# RiskChemi_Sensors_V2_11.net
KiCad netlist of a schematic drawn in Altium Designer
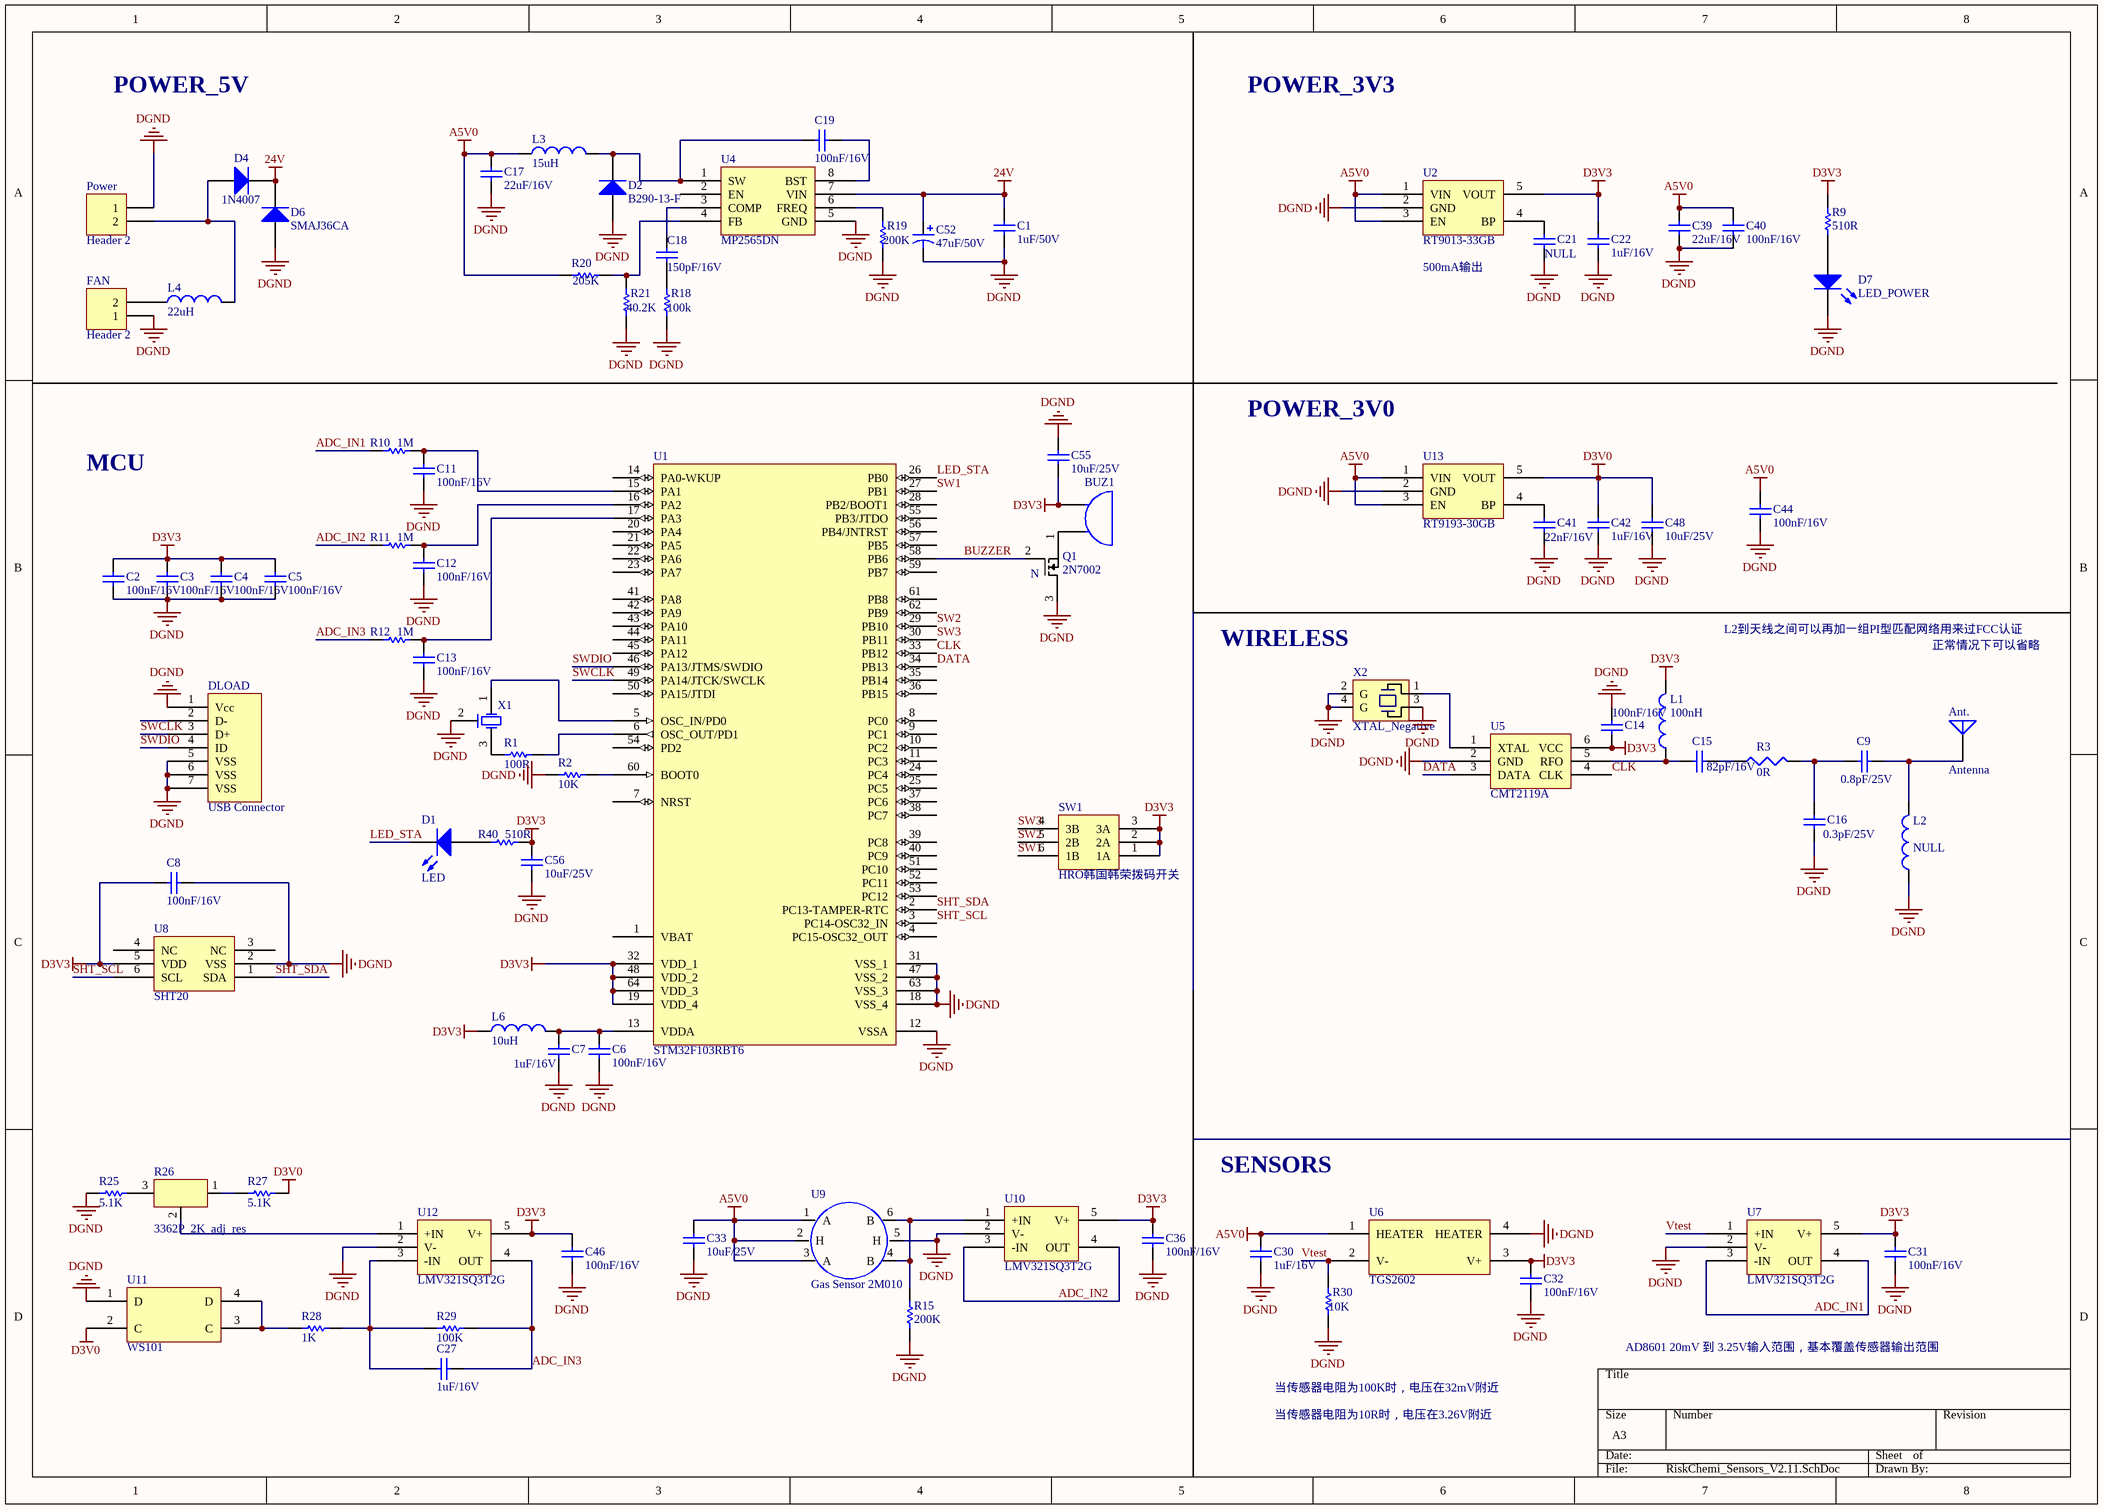
[diagram p0: RiskChemi_Sensors_V2.11.SchDoc]

(export (version "E")
  (design (tool "Eeschema 10.0.6"))
  (components
    (comp (ref "Ant.")
      (value "Antenna")
      (footprint "PIN1")
      (description "Generic Antenna")
      (fields (field (name "PUBLISHER") "Altium Limited"))
      (libsource (lib "Miscellaneous Devices") (part "Antenna"))
    )
    (comp (ref "BUZ1")
      (value "BUZZER 0905 through hole")
      (footprint "BUZ0905")
      (description "Buzzer")
      (libsource (lib "杂元件库") (part "BUZZER"))
    )
    (comp (ref "C1")
      (value "1uF/50V")
      (footprint "0805")
      (description "Capacitor")
      (fields (field (name "PUBLISHER") "Altium Limited"))
      (libsource (lib "Miscellaneous Devices") (part "Cap"))
    )
    (comp (ref "C2")
      (value "100nF/16V")
      (footprint "BinFeng:0603")
      (description "Capacitor")
      (fields (field (name "PUBLISHER") "Altium Limited"))
      (libsource (lib "Miscellaneous Devices") (part "Cap"))
    )
    (comp (ref "C3")
      (value "100nF/16V")
      (footprint "BinFeng:0603")
      (description "Capacitor")
      (fields (field (name "PUBLISHER") "Altium Limited"))
      (libsource (lib "Miscellaneous Devices") (part "Cap"))
    )
    (comp (ref "C4")
      (value "100nF/16V")
      (footprint "BinFeng:0603")
      (description "Capacitor")
      (fields (field (name "PUBLISHER") "Altium Limited"))
      (libsource (lib "Miscellaneous Devices") (part "Cap"))
    )
    (comp (ref "C5")
      (value "100nF/16V")
      (footprint "BinFeng:0603")
      (description "Capacitor")
      (fields (field (name "PUBLISHER") "Altium Limited"))
      (libsource (lib "Miscellaneous Devices") (part "Cap"))
    )
    (comp (ref "C6")
      (value "100nF/16V")
      (footprint "BinFeng:0603")
      (description "Capacitor")
      (fields (field (name "PUBLISHER") "Altium Limited"))
      (libsource (lib "Miscellaneous Devices") (part "Cap"))
    )
    (comp (ref "C7")
      (value "1uF/16V")
      (footprint "BinFeng:0603")
      (description "Capacitor")
      (fields (field (name "PUBLISHER") "Altium Limited"))
      (libsource (lib "Miscellaneous Devices") (part "Cap"))
    )
    (comp (ref "C8")
      (value "100nF/16V")
      (footprint "BinFeng:0603")
      (description "Capacitor")
      (fields (field (name "PUBLISHER") "Altium Limited"))
      (libsource (lib "Miscellaneous Devices") (part "Cap"))
    )
    (comp (ref "C9")
      (value "0.8pF/25V")
      (footprint "1608[0603]")
      (description "Capacitor (Semiconductor SIM Model)")
      (fields (field (name "PUBLISHER") "Altium Limited"))
      (libsource (lib "Miscellaneous Devices") (part "Cap Semi"))
    )
    (comp (ref "C11")
      (value "100nF/16V")
      (footprint "BinFeng:0603")
      (description "Capacitor")
      (fields (field (name "PUBLISHER") "Altium Limited"))
      (libsource (lib "Miscellaneous Devices") (part "Cap"))
    )
    (comp (ref "C12")
      (value "100nF/16V")
      (footprint "BinFeng:0603")
      (description "Capacitor")
      (fields (field (name "PUBLISHER") "Altium Limited"))
      (libsource (lib "Miscellaneous Devices") (part "Cap"))
    )
    (comp (ref "C13")
      (value "100nF/16V")
      (footprint "BinFeng:0603")
      (description "Capacitor")
      (fields (field (name "PUBLISHER") "Altium Limited"))
      (libsource (lib "Miscellaneous Devices") (part "Cap"))
    )
    (comp (ref "C14")
      (value "100nF/16V")
      (footprint "BinFeng:0402")
      (description "Capacitor")
      (fields (field (name "PUBLISHER") "Altium Limited"))
      (libsource (lib "Miscellaneous Devices") (part "Cap"))
    )
    (comp (ref "C15")
      (value "82pF/16V")
      (footprint "BinFeng:0402")
      (description "Capacitor")
      (fields (field (name "PUBLISHER") "Altium Limited"))
      (libsource (lib "Miscellaneous Devices") (part "Cap"))
    )
    (comp (ref "C16")
      (value "0.3pF/25V")
      (footprint "BinFeng:0402")
      (description "Capacitor")
      (fields (field (name "PUBLISHER") "Altium Limited"))
      (libsource (lib "Miscellaneous Devices") (part "Cap"))
    )
    (comp (ref "C17")
      (value "22uF/16V")
      (footprint "0805")
      (description "Capacitor,50V")
      (fields (field (name "PUBLISHER") "Altium Limited"))
      (libsource (lib "Miscellaneous Devices") (part "Cap"))
    )
    (comp (ref "C18")
      (value "150pF/16V")
      (footprint "BinFeng:0603")
      (description "Capacitor")
      (fields (field (name "PUBLISHER") "Altium Limited"))
      (libsource (lib "Miscellaneous Devices") (part "Cap"))
    )
    (comp (ref "C19")
      (value "100nF/16V")
      (footprint "BinFeng:0603")
      (description "Capacitor")
      (fields (field (name "PUBLISHER") "Altium Limited"))
      (libsource (lib "Miscellaneous Devices") (part "Cap"))
    )
    (comp (ref "C21")
      (value "NULL")
      (footprint "BinFeng:0402")
      (description "Capacitor")
      (fields (field (name "PUBLISHER") "Altium Limited"))
      (libsource (lib "Miscellaneous Devices") (part "Cap"))
    )
    (comp (ref "C22")
      (value "1uF/16V")
      (footprint "BinFeng:0402")
      (description "Capacitor")
      (fields (field (name "PUBLISHER") "Altium Limited"))
      (libsource (lib "Miscellaneous Devices") (part "Cap"))
    )
    (comp (ref "C27")
      (value "1uF/16V")
      (footprint "BinFeng:0603")
      (description "Capacitor")
      (fields (field (name "PUBLISHER") "Altium Limited"))
      (libsource (lib "Miscellaneous Devices") (part "Cap"))
    )
    (comp (ref "C30")
      (value "1uF/16V")
      (footprint "BinFeng:0603")
      (description "Capacitor")
      (fields (field (name "PUBLISHER") "Altium Limited"))
      (libsource (lib "Miscellaneous Devices") (part "Cap"))
    )
    (comp (ref "C31")
      (value "100nF/16V")
      (footprint "BinFeng:0603")
      (description "Capacitor")
      (fields (field (name "PUBLISHER") "Altium Limited"))
      (libsource (lib "Miscellaneous Devices") (part "Cap"))
    )
    (comp (ref "C32")
      (value "100nF/16V")
      (footprint "BinFeng:0603")
      (description "Capacitor")
      (fields (field (name "PUBLISHER") "Altium Limited"))
      (libsource (lib "Miscellaneous Devices") (part "Cap"))
    )
    (comp (ref "C33")
      (value "10uF/25V")
      (footprint "0805")
      (description "Capacitor")
      (fields (field (name "PUBLISHER") "Altium Limited"))
      (libsource (lib "Miscellaneous Devices") (part "Cap"))
    )
    (comp (ref "C36")
      (value "100nF/16V")
      (footprint "BinFeng:0603")
      (description "Capacitor")
      (fields (field (name "PUBLISHER") "Altium Limited"))
      (libsource (lib "Miscellaneous Devices") (part "Cap"))
    )
    (comp (ref "C39")
      (value "22uF/16V")
      (footprint "1206")
      (description "Capacitor")
      (fields (field (name "PUBLISHER") "Altium Limited"))
      (libsource (lib "Miscellaneous Devices") (part "Cap"))
    )
    (comp (ref "C40")
      (value "100nF/16V")
      (footprint "BinFeng:0402")
      (description "Capacitor")
      (fields (field (name "PUBLISHER") "Altium Limited"))
      (libsource (lib "Miscellaneous Devices") (part "Cap"))
    )
    (comp (ref "C41")
      (value "22nF/16V")
      (footprint "BinFeng:0402")
      (description "Capacitor")
      (fields (field (name "PUBLISHER") "Altium Limited"))
      (libsource (lib "Miscellaneous Devices") (part "Cap"))
    )
    (comp (ref "C42")
      (value "1uF/16V")
      (footprint "BinFeng:0402")
      (description "Capacitor")
      (fields (field (name "PUBLISHER") "Altium Limited"))
      (libsource (lib "Miscellaneous Devices") (part "Cap"))
    )
    (comp (ref "C44")
      (value "100nF/16V")
      (footprint "BinFeng:0402")
      (description "Capacitor")
      (fields (field (name "PUBLISHER") "Altium Limited"))
      (libsource (lib "Miscellaneous Devices") (part "Cap"))
    )
    (comp (ref "C46")
      (value "100nF/16V")
      (footprint "BinFeng:0603")
      (description "Capacitor")
      (fields (field (name "PUBLISHER") "Altium Limited"))
      (libsource (lib "Miscellaneous Devices") (part "Cap"))
    )
    (comp (ref "C48")
      (value "10uF/25V")
      (footprint "0805")
      (description "Capacitor")
      (fields (field (name "PUBLISHER") "Altium Limited"))
      (libsource (lib "Miscellaneous Devices") (part "Cap"))
    )
    (comp (ref "C52")
      (value "47uF/50V")
      (footprint "cap_pol_8*10.2")
      (description "Polarized Capacitor (Radial)")
      (fields (field (name "PUBLISHER") "Altium Limited"))
      (libsource (lib "Miscellaneous Devices") (part "Cap Pol1"))
    )
    (comp (ref "C55")
      (value "10uF/25V")
      (footprint "0805")
      (description "Capacitor")
      (fields (field (name "PUBLISHER") "Altium Limited"))
      (libsource (lib "Miscellaneous Devices") (part "Cap"))
    )
    (comp (ref "C56")
      (value "10uF/25V")
      (footprint "0805")
      (description "Capacitor")
      (fields (field (name "PUBLISHER") "Altium Limited"))
      (libsource (lib "Miscellaneous Devices") (part "Cap"))
    )
    (comp (ref "D1")
      (value "LED")
      (footprint "1206_LED")
      (description "Typical INFRARED GaAs LED")
      (fields (field (name "PUBLISHER") "Altium Limited"))
      (libsource (lib "Miscellaneous Devices") (part "LED0"))
    )
    (comp (ref "D2")
      (value "B290-13-F")
      (footprint "B290")
      (description "Default Diode")
      (fields (field (name "PUBLISHER") "Altium Limited"))
      (libsource (lib "Miscellaneous Devices") (part "Diode"))
    )
    (comp (ref "D4")
      (value "1N4007")
      (footprint "6032_pol")
      (description "1 Amp General Purpose Rectifier")
      (fields (field (name "PUBLISHER") "Altium Limited"))
      (libsource (lib "Miscellaneous Devices") (part "Diode 1N4007"))
    )
    (comp (ref "D6")
      (value "SMAJ36CA")
      (footprint "B290")
      (description "1 Amp General Purpose Rectifier")
      (fields (field (name "PUBLISHER") "Altium Limited"))
      (libsource (lib "Miscellaneous Devices") (part "Diode 1N4007"))
    )
    (comp (ref "D7")
      (value "LED_POWER")
      (footprint "1206_LED")
      (description "Typical INFRARED GaAs LED")
      (fields (field (name "PUBLISHER") "Altium Limited"))
      (libsource (lib "Miscellaneous Devices") (part "LED0"))
    )
    (comp (ref "DLOAD")
      (value "USB Connector")
      (footprint "Mini_USB")
      (libsource (lib "BinFeng_Connectors") (part "Component_1"))
    )
    (comp (ref "FAN")
      (value "Header 2")
      (footprint "HDR1X2")
      (description "Header, 2-Pin")
      (fields (field (name "PUBLISHER") "Altium Limited"))
      (libsource (lib "") (part "Header 2_1"))
    )
    (comp (ref "L1")
      (value "100nH")
      (footprint "0603C")
      (description "Inductor")
      (fields (field (name "PUBLISHER") "Altium Limited"))
      (libsource (lib "Miscellaneous Devices") (part "Inductor"))
    )
    (comp (ref "L2")
      (value "NULL")
      (footprint "hg:0402")
      (description "Inductor")
      (fields (field (name "PUBLISHER") "Altium Limited"))
      (libsource (lib "Miscellaneous Devices") (part "Inductor"))
    )
    (comp (ref "L3")
      (value "15uH")
      (footprint "4*4 Inductor")
      (description "Inductor, 1A")
      (fields (field (name "PUBLISHER") "Altium Limited"))
      (libsource (lib "Miscellaneous Devices") (part "Inductor"))
    )
    (comp (ref "L4")
      (value "22uH")
      (footprint "10*10Inductor")
      (description "Inductor, 1A")
      (fields (field (name "PUBLISHER") "Altium Limited"))
      (libsource (lib "Miscellaneous Devices") (part "Inductor"))
    )
    (comp (ref "L6")
      (value "10uH")
      (footprint "0805")
      (description "Inductor")
      (fields (field (name "PUBLISHER") "Altium Limited"))
      (libsource (lib "Miscellaneous Devices") (part "Inductor"))
    )
    (comp (ref "Power")
      (value "Header 2")
      (footprint "HDR1X2")
      (description "Header, 2-Pin")
      (fields (field (name "PUBLISHER") "Altium Limited"))
      (libsource (lib "Miscellaneous Connectors") (part "Header 2"))
    )
    (comp (ref "Q1") (value "2N7002") (footprint "2N7002") (libsource (lib "seeder") (part "N-MOSFET")))
    (comp (ref "R1")
      (value "100R")
      (footprint "BinFeng:0603")
      (description "Resistor")
      (fields (field (name "PUBLISHER") "Altium Limited"))
      (libsource (lib "Miscellaneous Devices") (part "Res1"))
    )
    (comp (ref "R2")
      (value "10K")
      (footprint "BinFeng:0603")
      (description "Resistor")
      (fields (field (name "PUBLISHER") "Altium Limited"))
      (libsource (lib "Miscellaneous Devices") (part "Res1"))
    )
    (comp (ref "R3")
      (value "0R")
      (footprint "J1-0603")
      (description "Resistor")
      (fields (field (name "PUBLISHER") "Altium Limited"))
      (libsource (lib "Miscellaneous Devices") (part "Res3"))
    )
    (comp (ref "R9")
      (value "510R")
      (footprint "BinFeng:0603")
      (description "Resistor")
      (fields (field (name "PUBLISHER") "Altium Limited"))
      (libsource (lib "Miscellaneous Devices") (part "Res1"))
    )
    (comp (ref "R10")
      (value "1M")
      (footprint "BinFeng:0603")
      (description "Resistor")
      (fields (field (name "PUBLISHER") "Altium Limited"))
      (libsource (lib "Miscellaneous Devices") (part "Res1"))
    )
    (comp (ref "R11")
      (value "1M")
      (footprint "BinFeng:0603")
      (description "Resistor")
      (fields (field (name "PUBLISHER") "Altium Limited"))
      (libsource (lib "Miscellaneous Devices") (part "Res1"))
    )
    (comp (ref "R12")
      (value "1M")
      (footprint "BinFeng:0603")
      (description "Resistor")
      (fields (field (name "PUBLISHER") "Altium Limited"))
      (libsource (lib "Miscellaneous Devices") (part "Res1"))
    )
    (comp (ref "R15")
      (value "200K")
      (footprint "BinFeng:0603C")
      (description "Resistor")
      (fields (field (name "Comment") "Res1") (field (name "PUBLISHER") "Altium Limited"))
      (libsource (lib "Miscellaneous Devices") (part "Res1"))
    )
    (comp (ref "R18")
      (value "100k")
      (footprint "BinFeng:0603")
      (description "Resistor")
      (fields (field (name "PUBLISHER") "Altium Limited"))
      (libsource (lib "Miscellaneous Devices") (part "Res1"))
    )
    (comp (ref "R19")
      (value "200K")
      (footprint "BinFeng:0402")
      (description "Resistor")
      (fields (field (name "PUBLISHER") "Altium Limited"))
      (libsource (lib "Miscellaneous Devices") (part "Res1"))
    )
    (comp (ref "R20")
      (value "205K")
      (footprint "BinFeng:0603")
      (description "Resistor")
      (fields (field (name "PUBLISHER") "Altium Limited"))
      (libsource (lib "Miscellaneous Devices") (part "Res1"))
    )
    (comp (ref "R21")
      (value "40.2K")
      (footprint "BinFeng:0603")
      (description "Resistor")
      (fields (field (name "PUBLISHER") "Altium Limited"))
      (libsource (lib "Miscellaneous Devices") (part "Res1"))
    )
    (comp (ref "R25")
      (value "5.1K")
      (footprint "BinFeng:0603")
      (description "Resistor")
      (fields (field (name "PUBLISHER") "Altium Limited"))
      (libsource (lib "Miscellaneous Devices") (part "Res1"))
    )
    (comp (ref "R26")
      (value "3362P_2K_adj_res")
      (footprint "res_adj")
      (libsource (lib "BinFeng_IC") (part "res_adj"))
    )
    (comp (ref "R27")
      (value "5.1K")
      (footprint "BinFeng:0603")
      (description "Resistor")
      (fields (field (name "PUBLISHER") "Altium Limited"))
      (libsource (lib "Miscellaneous Devices") (part "Res1"))
    )
    (comp (ref "R28")
      (value "1K")
      (footprint "BinFeng:0603")
      (description "Resistor")
      (fields (field (name "PUBLISHER") "Altium Limited"))
      (libsource (lib "Miscellaneous Devices") (part "Res1"))
    )
    (comp (ref "R29")
      (value "100K")
      (footprint "BinFeng:0603")
      (description "Resistor")
      (fields (field (name "PUBLISHER") "Altium Limited"))
      (libsource (lib "Miscellaneous Devices") (part "Res1"))
    )
    (comp (ref "R30")
      (value "10K")
      (footprint "BinFeng:0603")
      (description "Resistor")
      (fields (field (name "PUBLISHER") "Altium Limited"))
      (libsource (lib "Miscellaneous Devices") (part "Res1"))
    )
    (comp (ref "R40")
      (value "510R")
      (footprint "BinFeng:0603")
      (description "Resistor")
      (fields (field (name "PUBLISHER") "Altium Limited"))
      (libsource (lib "Miscellaneous Devices") (part "Res1"))
    )
    (comp (ref "SW1")
      (value "HRO韩国韩荣拨码开关")
      (footprint "SW_6P_HRO")
      (libsource (lib "BinFeng_IC") (part "SW_6P"))
    )
    (comp (ref "U1")
      (value "STM32F103RBT6")
      (footprint "LQFP64_N")
      (description "STM32 ARM-based 32-bit MCU with 64 Kbytes Flash, 64-pin LQFP, Industrial Temperature")
      (fields (field (name "PUBLISHER") "Altium Limited"))
      (libsource (lib "ST Microcontroller 32-Bit STM32") (part "STM32F103R8T6"))
    )
    (comp (ref "U2")
      (value "RT9013-33GB")
      (footprint "SOT-23-5")
      (libsource (lib "BinFeng_IC") (part "RT9193"))
    )
    (comp (ref "U4")
      (value "MP2565DN")
      (footprint "so-8")
      (description "DCDC 4.5V~28V input 1.8V ~5V output low power")
      (libsource (lib "BinFeng_IC") (part "MP1584"))
    )
    (comp (ref "U5")
      (value "CMT2119A")
      (footprint "sot23-6")
      (libsource (lib "BinFeng_IC") (part "CMT2119A"))
    )
    (comp (ref "U6")
      (value "TGS2602")
      (footprint "Gas Sensor TGS2602 Slot")
      (description "VOC sensor")
      (libsource (lib "BinFeng_IC") (part "TGS2602"))
    )
    (comp (ref "U7")
      (value "LMV321SQ3T2G")
      (footprint "SC-70-5")
      (libsource (lib "BinFeng_IC") (part "LMV321SQ3T2G"))
    )
    (comp (ref "U8") (value "SHT20") (footprint "SHT20") (libsource (lib "BinFeng_IC") (part "SHT20")))
    (comp (ref "U9")
      (value "Gas Sensor 2M010")
      (footprint "Gas Sensor 2M010 Slot")
      (libsource (lib "BinFeng_IC") (part "Gas Sensor"))
    )
    (comp (ref "U10")
      (value "LMV321SQ3T2G")
      (footprint "SC-70-5")
      (libsource (lib "BinFeng_IC") (part "LMV321SQ3T2G"))
    )
    (comp (ref "U11")
      (value "WS101")
      (footprint "Gas_Sensor_WS101_Slot")
      (libsource (lib "BinFeng_IC") (part "Gas Sensor_WS101"))
    )
    (comp (ref "U12")
      (value "LMV321SQ3T2G")
      (footprint "SC-70-5")
      (libsource (lib "BinFeng_IC") (part "LMV321SQ3T2G"))
    )
    (comp (ref "U13")
      (value "RT9193-30GB")
      (footprint "SOT-23-5")
      (libsource (lib "BinFeng_IC") (part "RT9193"))
    )
    (comp (ref "X1") (value "8M smd") (footprint "8Mhz_XTAL") (libsource (lib "Schlib1") (part "8M smd")))
    (comp (ref "X2")
      (value "XTAL_Negative")
      (footprint "XTAL3225")
      (libsource (lib "BinFeng_IC") (part "XTAL_Negative"))
    )
  )
  (nets
    (net (code "1") (name "/ADC_IN1") (class "Default")
      (node (ref "R10") (pin "1") (pinfunction "1_1") (pintype "passive"))
      (node (ref "U7") (pin "3") (pinfunction "-IN_3") (pintype "passive"))
      (node (ref "U7") (pin "4") (pinfunction "OUT_4") (pintype "passive"))
    )
    (net (code "2") (name "/ADC_IN2") (class "Default")
      (node (ref "R11") (pin "1") (pinfunction "1_1") (pintype "passive"))
      (node (ref "U10") (pin "3") (pinfunction "-IN_3") (pintype "passive"))
      (node (ref "U10") (pin "4") (pinfunction "OUT_4") (pintype "passive"))
    )
    (net (code "3") (name "/ADC_IN3") (class "Default")
      (node (ref "C27") (pin "1") (pinfunction "1_1") (pintype "passive"))
      (node (ref "R12") (pin "1") (pinfunction "1_1") (pintype "passive"))
      (node (ref "R29") (pin "2") (pinfunction "2_2") (pintype "passive"))
      (node (ref "U12") (pin "4") (pinfunction "OUT_4") (pintype "passive"))
    )
    (net (code "4") (name "/BUZZER") (class "Default")
      (node (ref "Q1") (pin "2") (pinfunction "G_2") (pintype "passive"))
      (node (ref "U1") (pin "58") (pinfunction "PB6_58") (pintype "bidirectional"))
    )
    (net (code "5") (name "/CLK") (class "Default")
      (node (ref "U1") (pin "33") (pinfunction "PB12_33") (pintype "bidirectional"))
      (node (ref "U5") (pin "4") (pinfunction "CLK_4") (pintype "passive"))
    )
    (net (code "6") (name "/DATA") (class "Default")
      (node (ref "U1") (pin "34") (pinfunction "PB13_34") (pintype "bidirectional"))
      (node (ref "U5") (pin "3") (pinfunction "DATA_3") (pintype "passive"))
    )
    (net (code "7") (name "/LED_STA") (class "Default")
      (node (ref "D1") (pin "2") (pinfunction "K_2") (pintype "passive"))
      (node (ref "U1") (pin "26") (pinfunction "PB0_26") (pintype "bidirectional"))
    )
    (net (code "8") (name "/SHT_SCL") (class "Default")
      (node (ref "U1") (pin "3") (pinfunction "PC14-OSC32_IN_3") (pintype "bidirectional"))
      (node (ref "U8") (pin "6") (pinfunction "SCL_6") (pintype "passive"))
    )
    (net (code "9") (name "/SHT_SDA") (class "Default")
      (node (ref "U1") (pin "2") (pinfunction "PC13-TAMPER-RTC_2") (pintype "bidirectional"))
      (node (ref "U8") (pin "1") (pinfunction "SDA_1") (pintype "passive"))
    )
    (net (code "10") (name "/SW1") (class "Default")
      (node (ref "SW1") (pin "6") (pinfunction "1B_6") (pintype "passive"))
      (node (ref "U1") (pin "27") (pinfunction "PB1_27") (pintype "bidirectional"))
    )
    (net (code "11") (name "/SW2") (class "Default")
      (node (ref "SW1") (pin "5") (pinfunction "2B_5") (pintype "passive"))
      (node (ref "U1") (pin "29") (pinfunction "PB10_29") (pintype "bidirectional"))
    )
    (net (code "12") (name "/SW3") (class "Default")
      (node (ref "SW1") (pin "4") (pinfunction "3B_4") (pintype "passive"))
      (node (ref "U1") (pin "30") (pinfunction "PB11_30") (pintype "bidirectional"))
    )
    (net (code "13") (name "/SWCLK") (class "Default")
      (node (ref "DLOAD") (pin "3") (pinfunction "D+_3") (pintype "passive"))
      (node (ref "U1") (pin "49") (pinfunction "PA14/JTCK/SWCLK_49") (pintype "bidirectional"))
    )
    (net (code "14") (name "/SWDIO") (class "Default")
      (node (ref "DLOAD") (pin "4") (pinfunction "ID_4") (pintype "passive"))
      (node (ref "U1") (pin "46") (pinfunction "PA13/JTMS/SWDIO_46") (pintype "bidirectional"))
    )
    (net (code "15") (name "/Vtest") (class "Default")
      (node (ref "R30") (pin "2") (pinfunction "2_2") (pintype "passive"))
      (node (ref "U6") (pin "2") (pinfunction "V-_2") (pintype "passive"))
      (node (ref "U7") (pin "1") (pinfunction "+IN_1") (pintype "passive"))
    )
    (net (code "16") (name "24V") (class "Default")
      (node (ref "C1") (pin "2") (pinfunction "2_2") (pintype "passive"))
      (node (ref "C52") (pin "1") (pinfunction "1_1") (pintype "passive"))
      (node (ref "D4") (pin "2") (pinfunction "K_2") (pintype "passive"))
      (node (ref "D6") (pin "2") (pinfunction "K_2") (pintype "passive"))
      (node (ref "U4") (pin "7") (pinfunction "VIN_7") (pintype "passive"))
    )
    (net (code "17") (name "A5V0") (class "Default")
      (node (ref "C17") (pin "2") (pinfunction "2_2") (pintype "passive"))
      (node (ref "C30") (pin "2") (pinfunction "2_2") (pintype "passive"))
      (node (ref "C33") (pin "2") (pinfunction "2_2") (pintype "passive"))
      (node (ref "C39") (pin "1") (pinfunction "1_1") (pintype "passive"))
      (node (ref "C40") (pin "2") (pinfunction "2_2") (pintype "passive"))
      (node (ref "C44") (pin "2") (pinfunction "2_2") (pintype "passive"))
      (node (ref "L3") (pin "1") (pinfunction "1_1") (pintype "passive"))
      (node (ref "R20") (pin "2") (pinfunction "2_2") (pintype "passive"))
      (node (ref "U13") (pin "1") (pinfunction "VIN_1") (pintype "passive"))
      (node (ref "U13") (pin "3") (pinfunction "EN_3") (pintype "passive"))
      (node (ref "U2") (pin "1") (pinfunction "VIN_1") (pintype "passive"))
      (node (ref "U2") (pin "3") (pinfunction "EN_3") (pintype "passive"))
      (node (ref "U6") (pin "1") (pinfunction "HEATER_1") (pintype "passive"))
      (node (ref "U9") (pin "1") (pinfunction "A_1") (pintype "passive"))
      (node (ref "U9") (pin "2") (pinfunction "H_2") (pintype "passive"))
      (node (ref "U9") (pin "3") (pinfunction "A_3") (pintype "passive"))
    )
    (net (code "18") (name "D3V0") (class "Default")
      (node (ref "C42") (pin "2") (pinfunction "2_2") (pintype "passive"))
      (node (ref "C48") (pin "2") (pinfunction "2_2") (pintype "passive"))
      (node (ref "R27") (pin "2") (pinfunction "2_2") (pintype "passive"))
      (node (ref "U11") (pin "2") (pinfunction "C_2") (pintype "passive"))
      (node (ref "U13") (pin "5") (pinfunction "VOUT_5") (pintype "passive"))
    )
    (net (code "19") (name "D3V3") (class "Default")
      (node (ref "BUZ1") (pin "1") (pinfunction "A_1") (pintype "passive"))
      (node (ref "C14") (pin "2") (pinfunction "2_2") (pintype "passive"))
      (node (ref "C2") (pin "2") (pinfunction "2_2") (pintype "passive"))
      (node (ref "C22") (pin "2") (pinfunction "2_2") (pintype "passive"))
      (node (ref "C3") (pin "2") (pinfunction "2_2") (pintype "passive"))
      (node (ref "C31") (pin "2") (pinfunction "2_2") (pintype "passive"))
      (node (ref "C32") (pin "2") (pinfunction "2_2") (pintype "passive"))
      (node (ref "C36") (pin "2") (pinfunction "2_2") (pintype "passive"))
      (node (ref "C4") (pin "2") (pinfunction "2_2") (pintype "passive"))
      (node (ref "C46") (pin "2") (pinfunction "2_2") (pintype "passive"))
      (node (ref "C5") (pin "2") (pinfunction "2_2") (pintype "passive"))
      (node (ref "C55") (pin "2") (pinfunction "2_2") (pintype "passive"))
      (node (ref "C56") (pin "2") (pinfunction "2_2") (pintype "passive"))
      (node (ref "C8") (pin "2") (pinfunction "2_2") (pintype "passive"))
      (node (ref "L1") (pin "2") (pinfunction "2_2") (pintype "passive"))
      (node (ref "L6") (pin "1") (pinfunction "1_1") (pintype "passive"))
      (node (ref "R40") (pin "2") (pinfunction "2_2") (pintype "passive"))
      (node (ref "R9") (pin "2") (pinfunction "2_2") (pintype "passive"))
      (node (ref "SW1") (pin "1") (pinfunction "1A_1") (pintype "passive"))
      (node (ref "SW1") (pin "2") (pinfunction "2A_2") (pintype "passive"))
      (node (ref "SW1") (pin "3") (pinfunction "3A_3") (pintype "passive"))
      (node (ref "U1") (pin "19") (pinfunction "VDD_4_19") (pintype "power_in"))
      (node (ref "U1") (pin "32") (pinfunction "VDD_1_32") (pintype "power_in"))
      (node (ref "U1") (pin "48") (pinfunction "VDD_2_48") (pintype "power_in"))
      (node (ref "U1") (pin "64") (pinfunction "VDD_3_64") (pintype "power_in"))
      (node (ref "U10") (pin "5") (pinfunction "V+_5") (pintype "passive"))
      (node (ref "U12") (pin "5") (pinfunction "V+_5") (pintype "passive"))
      (node (ref "U2") (pin "5") (pinfunction "VOUT_5") (pintype "passive"))
      (node (ref "U5") (pin "6") (pinfunction "VCC_6") (pintype "passive"))
      (node (ref "U6") (pin "3") (pinfunction "V+_3") (pintype "passive"))
      (node (ref "U7") (pin "5") (pinfunction "V+_5") (pintype "passive"))
      (node (ref "U8") (pin "5") (pinfunction "VDD_5") (pintype "passive"))
    )
    (net (code "20") (name "DGND") (class "Default")
      (node (ref "C1") (pin "1") (pinfunction "1_1") (pintype "passive"))
      (node (ref "C11") (pin "2") (pinfunction "2_2") (pintype "passive"))
      (node (ref "C12") (pin "1") (pinfunction "1_1") (pintype "passive"))
      (node (ref "C13") (pin "1") (pinfunction "1_1") (pintype "passive"))
      (node (ref "C14") (pin "1") (pinfunction "1_1") (pintype "passive"))
      (node (ref "C16") (pin "1") (pinfunction "1_1") (pintype "passive"))
      (node (ref "C17") (pin "1") (pinfunction "1_1") (pintype "passive"))
      (node (ref "C2") (pin "1") (pinfunction "1_1") (pintype "passive"))
      (node (ref "C21") (pin "1") (pinfunction "1_1") (pintype "passive"))
      (node (ref "C22") (pin "1") (pinfunction "1_1") (pintype "passive"))
      (node (ref "C3") (pin "1") (pinfunction "1_1") (pintype "passive"))
      (node (ref "C30") (pin "1") (pinfunction "1_1") (pintype "passive"))
      (node (ref "C31") (pin "1") (pinfunction "1_1") (pintype "passive"))
      (node (ref "C32") (pin "1") (pinfunction "1_1") (pintype "passive"))
      (node (ref "C33") (pin "1") (pinfunction "1_1") (pintype "passive"))
      (node (ref "C36") (pin "1") (pinfunction "1_1") (pintype "passive"))
      (node (ref "C39") (pin "2") (pinfunction "2_2") (pintype "passive"))
      (node (ref "C4") (pin "1") (pinfunction "1_1") (pintype "passive"))
      (node (ref "C40") (pin "1") (pinfunction "1_1") (pintype "passive"))
      (node (ref "C41") (pin "1") (pinfunction "1_1") (pintype "passive"))
      (node (ref "C42") (pin "1") (pinfunction "1_1") (pintype "passive"))
      (node (ref "C44") (pin "1") (pinfunction "1_1") (pintype "passive"))
      (node (ref "C46") (pin "1") (pinfunction "1_1") (pintype "passive"))
      (node (ref "C48") (pin "1") (pinfunction "1_1") (pintype "passive"))
      (node (ref "C5") (pin "1") (pinfunction "1_1") (pintype "passive"))
      (node (ref "C52") (pin "2") (pinfunction "2_2") (pintype "passive"))
      (node (ref "C55") (pin "1") (pinfunction "1_1") (pintype "passive"))
      (node (ref "C56") (pin "1") (pinfunction "1_1") (pintype "passive"))
      (node (ref "C6") (pin "1") (pinfunction "1_1") (pintype "passive"))
      (node (ref "C7") (pin "1") (pinfunction "1_1") (pintype "passive"))
      (node (ref "C8") (pin "1") (pinfunction "1_1") (pintype "passive"))
      (node (ref "D2") (pin "1") (pinfunction "A_1") (pintype "passive"))
      (node (ref "D6") (pin "1") (pinfunction "A_1") (pintype "passive"))
      (node (ref "D7") (pin "2") (pinfunction "K_2") (pintype "passive"))
      (node (ref "DLOAD") (pin "1") (pinfunction "Vcc_1") (pintype "passive"))
      (node (ref "DLOAD") (pin "5") (pinfunction "VSS_5") (pintype "passive"))
      (node (ref "DLOAD") (pin "6") (pinfunction "VSS_6") (pintype "passive"))
      (node (ref "DLOAD") (pin "7") (pinfunction "VSS_7") (pintype "passive"))
      (node (ref "FAN") (pin "1") (pinfunction "1_1") (pintype "passive"))
      (node (ref "L2") (pin "1") (pinfunction "1_1") (pintype "passive"))
      (node (ref "Power") (pin "1") (pinfunction "1_1") (pintype "passive"))
      (node (ref "Q1") (pin "3") (pinfunction "S_3") (pintype "passive"))
      (node (ref "R15") (pin "2") (pinfunction "2_2") (pintype "passive"))
      (node (ref "R18") (pin "1") (pinfunction "1_1") (pintype "passive"))
      (node (ref "R19") (pin "1") (pinfunction "1_1") (pintype "passive"))
      (node (ref "R2") (pin "1") (pinfunction "1_1") (pintype "passive"))
      (node (ref "R21") (pin "1") (pinfunction "1_1") (pintype "passive"))
      (node (ref "R25") (pin "1") (pinfunction "1_1") (pintype "passive"))
      (node (ref "R30") (pin "1") (pinfunction "1_1") (pintype "passive"))
      (node (ref "U1") (pin "12") (pinfunction "VSSA_12") (pintype "power_in"))
      (node (ref "U1") (pin "18") (pinfunction "VSS_4_18") (pintype "power_in"))
      (node (ref "U1") (pin "31") (pinfunction "VSS_1_31") (pintype "power_in"))
      (node (ref "U1") (pin "47") (pinfunction "VSS_2_47") (pintype "power_in"))
      (node (ref "U1") (pin "63") (pinfunction "VSS_3_63") (pintype "power_in"))
      (node (ref "U10") (pin "2") (pinfunction "V-_2") (pintype "passive"))
      (node (ref "U11") (pin "1") (pinfunction "D_1") (pintype "passive"))
      (node (ref "U12") (pin "2") (pinfunction "V-_2") (pintype "passive"))
      (node (ref "U13") (pin "2") (pinfunction "GND_2") (pintype "passive"))
      (node (ref "U2") (pin "2") (pinfunction "GND_2") (pintype "passive"))
      (node (ref "U4") (pin "5") (pinfunction "GND_5") (pintype "passive"))
      (node (ref "U5") (pin "2") (pinfunction "GND_2") (pintype "passive"))
      (node (ref "U6") (pin "4") (pinfunction "HEATER_4") (pintype "passive"))
      (node (ref "U7") (pin "2") (pinfunction "V-_2") (pintype "passive"))
      (node (ref "U8") (pin "2") (pinfunction "VSS_2") (pintype "passive"))
      (node (ref "U9") (pin "5") (pinfunction "H_5") (pintype "passive"))
      (node (ref "X1") (pin "2") (pinfunction "GND_2") (pintype "passive"))
      (node (ref "X2") (pin "2") (pinfunction "G_2") (pintype "passive"))
      (node (ref "X2") (pin "3") (pintype "passive"))
      (node (ref "X2") (pin "4") (pinfunction "G_4") (pintype "passive"))
    )
    (net (code "21") (name "Net-(Ant.-A)") (class "Default")
      (node (ref "Ant.") (pin "1") (pinfunction "A_1") (pintype "passive"))
      (node (ref "C9") (pin "2") (pinfunction "2_2") (pintype "passive"))
      (node (ref "L2") (pin "2") (pinfunction "2_2") (pintype "passive"))
    )
    (net (code "22") (name "Net-(BUZ1-B)") (class "Default")
      (node (ref "BUZ1") (pin "2") (pinfunction "B_2") (pintype "passive"))
      (node (ref "Q1") (pin "1") (pinfunction "D_1") (pintype "passive"))
    )
    (net (code "23") (name "Net-(C15-Pad2)") (class "Default")
      (node (ref "C15") (pin "2") (pinfunction "2_2") (pintype "passive"))
      (node (ref "R3") (pin "1") (pinfunction "1_1") (pintype "passive"))
    )
    (net (code "24") (name "Net-(C16-Pad2)") (class "Default")
      (node (ref "C16") (pin "2") (pinfunction "2_2") (pintype "passive"))
      (node (ref "C9") (pin "1") (pinfunction "1_1") (pintype "passive"))
      (node (ref "R3") (pin "2") (pinfunction "2_2") (pintype "passive"))
    )
    (net (code "25") (name "Net-(C18-Pad2)") (class "Default")
      (node (ref "C18") (pin "2") (pinfunction "2_2") (pintype "passive"))
      (node (ref "R18") (pin "2") (pinfunction "2_2") (pintype "passive"))
    )
    (net (code "26") (name "Net-(D1-A)") (class "Default")
      (node (ref "D1") (pin "1") (pinfunction "A_1") (pintype "passive"))
      (node (ref "R40") (pin "1") (pinfunction "1_1") (pintype "passive"))
    )
    (net (code "27") (name "Net-(D2-K)") (class "Default")
      (node (ref "C19") (pin "2") (pinfunction "2_2") (pintype "passive"))
      (node (ref "D2") (pin "2") (pinfunction "K_2") (pintype "passive"))
      (node (ref "L3") (pin "2") (pinfunction "2_2") (pintype "passive"))
      (node (ref "U4") (pin "1") (pinfunction "SW_1") (pintype "passive"))
    )
    (net (code "28") (name "Net-(D4-A)") (class "Default")
      (node (ref "D4") (pin "1") (pinfunction "A_1") (pintype "passive"))
      (node (ref "L4") (pin "2") (pinfunction "2_2") (pintype "passive"))
      (node (ref "Power") (pin "2") (pinfunction "2_2") (pintype "passive"))
    )
    (net (code "29") (name "Net-(D7-A)") (class "Default")
      (node (ref "D7") (pin "1") (pinfunction "A_1") (pintype "passive"))
      (node (ref "R9") (pin "1") (pinfunction "1_1") (pintype "passive"))
    )
    (net (code "30") (name "Net-(FAN-Pad2)") (class "Default")
      (node (ref "FAN") (pin "2") (pinfunction "2_2") (pintype "passive"))
      (node (ref "L4") (pin "1") (pinfunction "1_1") (pintype "passive"))
    )
    (net (code "31") (name "Net-(R25-Pad2)") (class "Default")
      (node (ref "R25") (pin "2") (pinfunction "2_2") (pintype "passive"))
      (node (ref "R26") (pin "3") (pintype "passive"))
    )
    (net (code "32") (name "Net-(R26-Pad1)") (class "Default")
      (node (ref "R26") (pin "1") (pintype "passive"))
      (node (ref "R27") (pin "1") (pinfunction "1_1") (pintype "passive"))
    )
    (net (code "33") (name "Net-(R28-Pad1)") (class "Default")
      (node (ref "R28") (pin "1") (pinfunction "1_1") (pintype "passive"))
      (node (ref "U11") (pin "3") (pinfunction "C_3") (pintype "passive"))
      (node (ref "U11") (pin "4") (pinfunction "D_4") (pintype "passive"))
    )
    (net (code "34") (name "Net-(U1-BOOT0)") (class "Default")
      (node (ref "R2") (pin "2") (pinfunction "2_2") (pintype "passive"))
      (node (ref "U1") (pin "60") (pinfunction "BOOT0_60") (pintype "input"))
    )
    (net (code "35") (name "Net-(U1-OSC_IN{slash}PD0)") (class "Default")
      (node (ref "U1") (pin "5") (pinfunction "OSC_IN/PD0_5") (pintype "input"))
      (node (ref "X1") (pin "1") (pinfunction "OSC1_1") (pintype "passive"))
    )
    (net (code "36") (name "Net-(U1-OSC_OUT{slash}PD1)") (class "Default")
      (node (ref "R1") (pin "2") (pinfunction "2_2") (pintype "passive"))
      (node (ref "U1") (pin "6") (pinfunction "OSC_OUT/PD1_6") (pintype "output"))
    )
    (net (code "37") (name "Net-(U1-PA1)") (class "Default")
      (node (ref "C11") (pin "1") (pinfunction "1_1") (pintype "passive"))
      (node (ref "R10") (pin "2") (pinfunction "2_2") (pintype "passive"))
      (node (ref "U1") (pin "15") (pinfunction "PA1_15") (pintype "bidirectional"))
    )
    (net (code "38") (name "Net-(U1-PA2)") (class "Default")
      (node (ref "C12") (pin "2") (pinfunction "2_2") (pintype "passive"))
      (node (ref "R11") (pin "2") (pinfunction "2_2") (pintype "passive"))
      (node (ref "U1") (pin "16") (pinfunction "PA2_16") (pintype "bidirectional"))
    )
    (net (code "39") (name "Net-(U1-PA3)") (class "Default")
      (node (ref "C13") (pin "2") (pinfunction "2_2") (pintype "passive"))
      (node (ref "R12") (pin "2") (pinfunction "2_2") (pintype "passive"))
      (node (ref "U1") (pin "17") (pinfunction "PA3_17") (pintype "bidirectional"))
    )
    (net (code "40") (name "Net-(U1-VDDA)") (class "Default")
      (node (ref "C6") (pin "2") (pinfunction "2_2") (pintype "passive"))
      (node (ref "C7") (pin "2") (pinfunction "2_2") (pintype "passive"))
      (node (ref "L6") (pin "2") (pinfunction "2_2") (pintype "passive"))
      (node (ref "U1") (pin "13") (pinfunction "VDDA_13") (pintype "power_in"))
    )
    (net (code "41") (name "Net-(U2-BP)") (class "Default")
      (node (ref "C21") (pin "2") (pinfunction "2_2") (pintype "passive"))
      (node (ref "U2") (pin "4") (pinfunction "BP_4") (pintype "passive"))
    )
    (net (code "42") (name "Net-(U4-BST)") (class "Default")
      (node (ref "C19") (pin "1") (pinfunction "1_1") (pintype "passive"))
      (node (ref "U4") (pin "8") (pinfunction "BST_8") (pintype "passive"))
    )
    (net (code "43") (name "Net-(U4-COMP)") (class "Default")
      (node (ref "C18") (pin "1") (pinfunction "1_1") (pintype "passive"))
      (node (ref "U4") (pin "3") (pinfunction "COMP_3") (pintype "passive"))
    )
    (net (code "44") (name "Net-(U4-FB)") (class "Default")
      (node (ref "R20") (pin "1") (pinfunction "1_1") (pintype "passive"))
      (node (ref "R21") (pin "2") (pinfunction "2_2") (pintype "passive"))
      (node (ref "U4") (pin "4") (pinfunction "FB_4") (pintype "passive"))
    )
    (net (code "45") (name "Net-(U4-FREQ)") (class "Default")
      (node (ref "R19") (pin "2") (pinfunction "2_2") (pintype "passive"))
      (node (ref "U4") (pin "6") (pinfunction "FREQ_6") (pintype "passive"))
    )
    (net (code "46") (name "Net-(U5-RFO)") (class "Default")
      (node (ref "C15") (pin "1") (pinfunction "1_1") (pintype "passive"))
      (node (ref "L1") (pin "1") (pinfunction "1_1") (pintype "passive"))
      (node (ref "U5") (pin "5") (pinfunction "RFO_5") (pintype "passive"))
    )
    (net (code "47") (name "Net-(U5-XTAL)") (class "Default")
      (node (ref "U5") (pin "1") (pinfunction "XTAL_1") (pintype "passive"))
      (node (ref "X2") (pin "1") (pintype "passive"))
    )
    (net (code "48") (name "Net-(U10-+IN)") (class "Default")
      (node (ref "R15") (pin "1") (pinfunction "1_1") (pintype "passive"))
      (node (ref "U10") (pin "1") (pinfunction "+IN_1") (pintype "passive"))
      (node (ref "U9") (pin "4") (pinfunction "B_4") (pintype "passive"))
      (node (ref "U9") (pin "6") (pinfunction "B_6") (pintype "passive"))
    )
    (net (code "49") (name "Net-(U12-+IN)") (class "Default")
      (node (ref "R26") (pin "2") (pintype "passive"))
      (node (ref "U12") (pin "1") (pinfunction "+IN_1") (pintype "passive"))
    )
    (net (code "50") (name "Net-(U12--IN)") (class "Default")
      (node (ref "C27") (pin "2") (pinfunction "2_2") (pintype "passive"))
      (node (ref "R28") (pin "2") (pinfunction "2_2") (pintype "passive"))
      (node (ref "R29") (pin "1") (pinfunction "1_1") (pintype "passive"))
      (node (ref "U12") (pin "3") (pinfunction "-IN_3") (pintype "passive"))
    )
    (net (code "51") (name "Net-(U13-BP)") (class "Default")
      (node (ref "C41") (pin "2") (pinfunction "2_2") (pintype "passive"))
      (node (ref "U13") (pin "4") (pinfunction "BP_4") (pintype "passive"))
    )
    (net (code "52") (name "Net-(X1-OSC2)") (class "Default")
      (node (ref "R1") (pin "1") (pinfunction "1_1") (pintype "passive"))
      (node (ref "X1") (pin "3") (pinfunction "OSC2_3") (pintype "passive"))
    )
    (net (code "53") (name "unconnected-(DLOAD-D--Pad2)") (class "Default")
      (node (ref "DLOAD") (pin "2") (pinfunction "D-_2") (pintype "passive"))
    )
    (net (code "54") (name "unconnected-(U1-NRST-Pad7)") (class "Default")
      (node (ref "U1") (pin "7") (pinfunction "NRST_7") (pintype "bidirectional"))
    )
    (net (code "55") (name "unconnected-(U1-PA0-WKUP-Pad14)") (class "Default")
      (node (ref "U1") (pin "14") (pinfunction "PA0-WKUP_14") (pintype "bidirectional"))
    )
    (net (code "56") (name "unconnected-(U1-PA4-Pad20)") (class "Default")
      (node (ref "U1") (pin "20") (pinfunction "PA4_20") (pintype "bidirectional"))
    )
    (net (code "57") (name "unconnected-(U1-PA5-Pad21)") (class "Default")
      (node (ref "U1") (pin "21") (pinfunction "PA5_21") (pintype "bidirectional"))
    )
    (net (code "58") (name "unconnected-(U1-PA6-Pad22)") (class "Default")
      (node (ref "U1") (pin "22") (pinfunction "PA6_22") (pintype "bidirectional"))
    )
    (net (code "59") (name "unconnected-(U1-PA7-Pad23)") (class "Default")
      (node (ref "U1") (pin "23") (pinfunction "PA7_23") (pintype "bidirectional"))
    )
    (net (code "60") (name "unconnected-(U1-PA8-Pad41)") (class "Default")
      (node (ref "U1") (pin "41") (pinfunction "PA8_41") (pintype "bidirectional"))
    )
    (net (code "61") (name "unconnected-(U1-PA9-Pad42)") (class "Default")
      (node (ref "U1") (pin "42") (pinfunction "PA9_42") (pintype "bidirectional"))
    )
    (net (code "62") (name "unconnected-(U1-PA10-Pad43)") (class "Default")
      (node (ref "U1") (pin "43") (pinfunction "PA10_43") (pintype "bidirectional"))
    )
    (net (code "63") (name "unconnected-(U1-PA11-Pad44)") (class "Default")
      (node (ref "U1") (pin "44") (pinfunction "PA11_44") (pintype "bidirectional"))
    )
    (net (code "64") (name "unconnected-(U1-PA12-Pad45)") (class "Default")
      (node (ref "U1") (pin "45") (pinfunction "PA12_45") (pintype "bidirectional"))
    )
    (net (code "65") (name "unconnected-(U1-PA15{slash}JTDI-Pad50)") (class "Default")
      (node (ref "U1") (pin "50") (pinfunction "PA15/JTDI_50") (pintype "bidirectional"))
    )
    (net (code "66") (name "unconnected-(U1-PB2{slash}BOOT1-Pad28)") (class "Default")
      (node (ref "U1") (pin "28") (pinfunction "PB2/BOOT1_28") (pintype "bidirectional"))
    )
    (net (code "67") (name "unconnected-(U1-PB3{slash}JTDO-Pad55)") (class "Default")
      (node (ref "U1") (pin "55") (pinfunction "PB3/JTDO_55") (pintype "bidirectional"))
    )
    (net (code "68") (name "unconnected-(U1-PB4{slash}JNTRST-Pad56)") (class "Default")
      (node (ref "U1") (pin "56") (pinfunction "PB4/JNTRST_56") (pintype "bidirectional"))
    )
    (net (code "69") (name "unconnected-(U1-PB5-Pad57)") (class "Default")
      (node (ref "U1") (pin "57") (pinfunction "PB5_57") (pintype "bidirectional"))
    )
    (net (code "70") (name "unconnected-(U1-PB7-Pad59)") (class "Default")
      (node (ref "U1") (pin "59") (pinfunction "PB7_59") (pintype "bidirectional"))
    )
    (net (code "71") (name "unconnected-(U1-PB8-Pad61)") (class "Default")
      (node (ref "U1") (pin "61") (pinfunction "PB8_61") (pintype "bidirectional"))
    )
    (net (code "72") (name "unconnected-(U1-PB9-Pad62)") (class "Default")
      (node (ref "U1") (pin "62") (pinfunction "PB9_62") (pintype "bidirectional"))
    )
    (net (code "73") (name "unconnected-(U1-PB14-Pad35)") (class "Default")
      (node (ref "U1") (pin "35") (pinfunction "PB14_35") (pintype "bidirectional"))
    )
    (net (code "74") (name "unconnected-(U1-PB15-Pad36)") (class "Default")
      (node (ref "U1") (pin "36") (pinfunction "PB15_36") (pintype "bidirectional"))
    )
    (net (code "75") (name "unconnected-(U1-PC0-Pad8)") (class "Default")
      (node (ref "U1") (pin "8") (pinfunction "PC0_8") (pintype "bidirectional"))
    )
    (net (code "76") (name "unconnected-(U1-PC1-Pad9)") (class "Default")
      (node (ref "U1") (pin "9") (pinfunction "PC1_9") (pintype "bidirectional"))
    )
    (net (code "77") (name "unconnected-(U1-PC2-Pad10)") (class "Default")
      (node (ref "U1") (pin "10") (pinfunction "PC2_10") (pintype "bidirectional"))
    )
    (net (code "78") (name "unconnected-(U1-PC3-Pad11)") (class "Default")
      (node (ref "U1") (pin "11") (pinfunction "PC3_11") (pintype "bidirectional"))
    )
    (net (code "79") (name "unconnected-(U1-PC4-Pad24)") (class "Default")
      (node (ref "U1") (pin "24") (pinfunction "PC4_24") (pintype "bidirectional"))
    )
    (net (code "80") (name "unconnected-(U1-PC5-Pad25)") (class "Default")
      (node (ref "U1") (pin "25") (pinfunction "PC5_25") (pintype "bidirectional"))
    )
    (net (code "81") (name "unconnected-(U1-PC6-Pad37)") (class "Default")
      (node (ref "U1") (pin "37") (pinfunction "PC6_37") (pintype "bidirectional"))
    )
    (net (code "82") (name "unconnected-(U1-PC7-Pad38)") (class "Default")
      (node (ref "U1") (pin "38") (pinfunction "PC7_38") (pintype "bidirectional"))
    )
    (net (code "83") (name "unconnected-(U1-PC8-Pad39)") (class "Default")
      (node (ref "U1") (pin "39") (pinfunction "PC8_39") (pintype "bidirectional"))
    )
    (net (code "84") (name "unconnected-(U1-PC9-Pad40)") (class "Default")
      (node (ref "U1") (pin "40") (pinfunction "PC9_40") (pintype "bidirectional"))
    )
    (net (code "85") (name "unconnected-(U1-PC10-Pad51)") (class "Default")
      (node (ref "U1") (pin "51") (pinfunction "PC10_51") (pintype "bidirectional"))
    )
    (net (code "86") (name "unconnected-(U1-PC11-Pad52)") (class "Default")
      (node (ref "U1") (pin "52") (pinfunction "PC11_52") (pintype "bidirectional"))
    )
    (net (code "87") (name "unconnected-(U1-PC12-Pad53)") (class "Default")
      (node (ref "U1") (pin "53") (pinfunction "PC12_53") (pintype "bidirectional"))
    )
    (net (code "88") (name "unconnected-(U1-PC15-OSC32_OUT-Pad4)") (class "Default")
      (node (ref "U1") (pin "4") (pinfunction "PC15-OSC32_OUT_4") (pintype "bidirectional"))
    )
    (net (code "89") (name "unconnected-(U1-PD2-Pad54)") (class "Default")
      (node (ref "U1") (pin "54") (pinfunction "PD2_54") (pintype "bidirectional"))
    )
    (net (code "90") (name "unconnected-(U1-VBAT-Pad1)") (class "Default")
      (node (ref "U1") (pin "1") (pinfunction "VBAT_1") (pintype "power_in"))
    )
    (net (code "91") (name "unconnected-(U4-EN-Pad2)") (class "Default")
      (node (ref "U4") (pin "2") (pinfunction "EN_2") (pintype "passive"))
    )
    (net (code "92") (name "unconnected-(U8-NC-Pad3)") (class "Default")
      (node (ref "U8") (pin "3") (pinfunction "NC_3") (pintype "passive"))
    )
    (net (code "93") (name "unconnected-(U8-NC-Pad4)") (class "Default")
      (node (ref "U8") (pin "4") (pinfunction "NC_4") (pintype "passive"))
    )
  )
)
